# BIT_4.net
KiCad netlist of a schematic drawn in EasyEDA
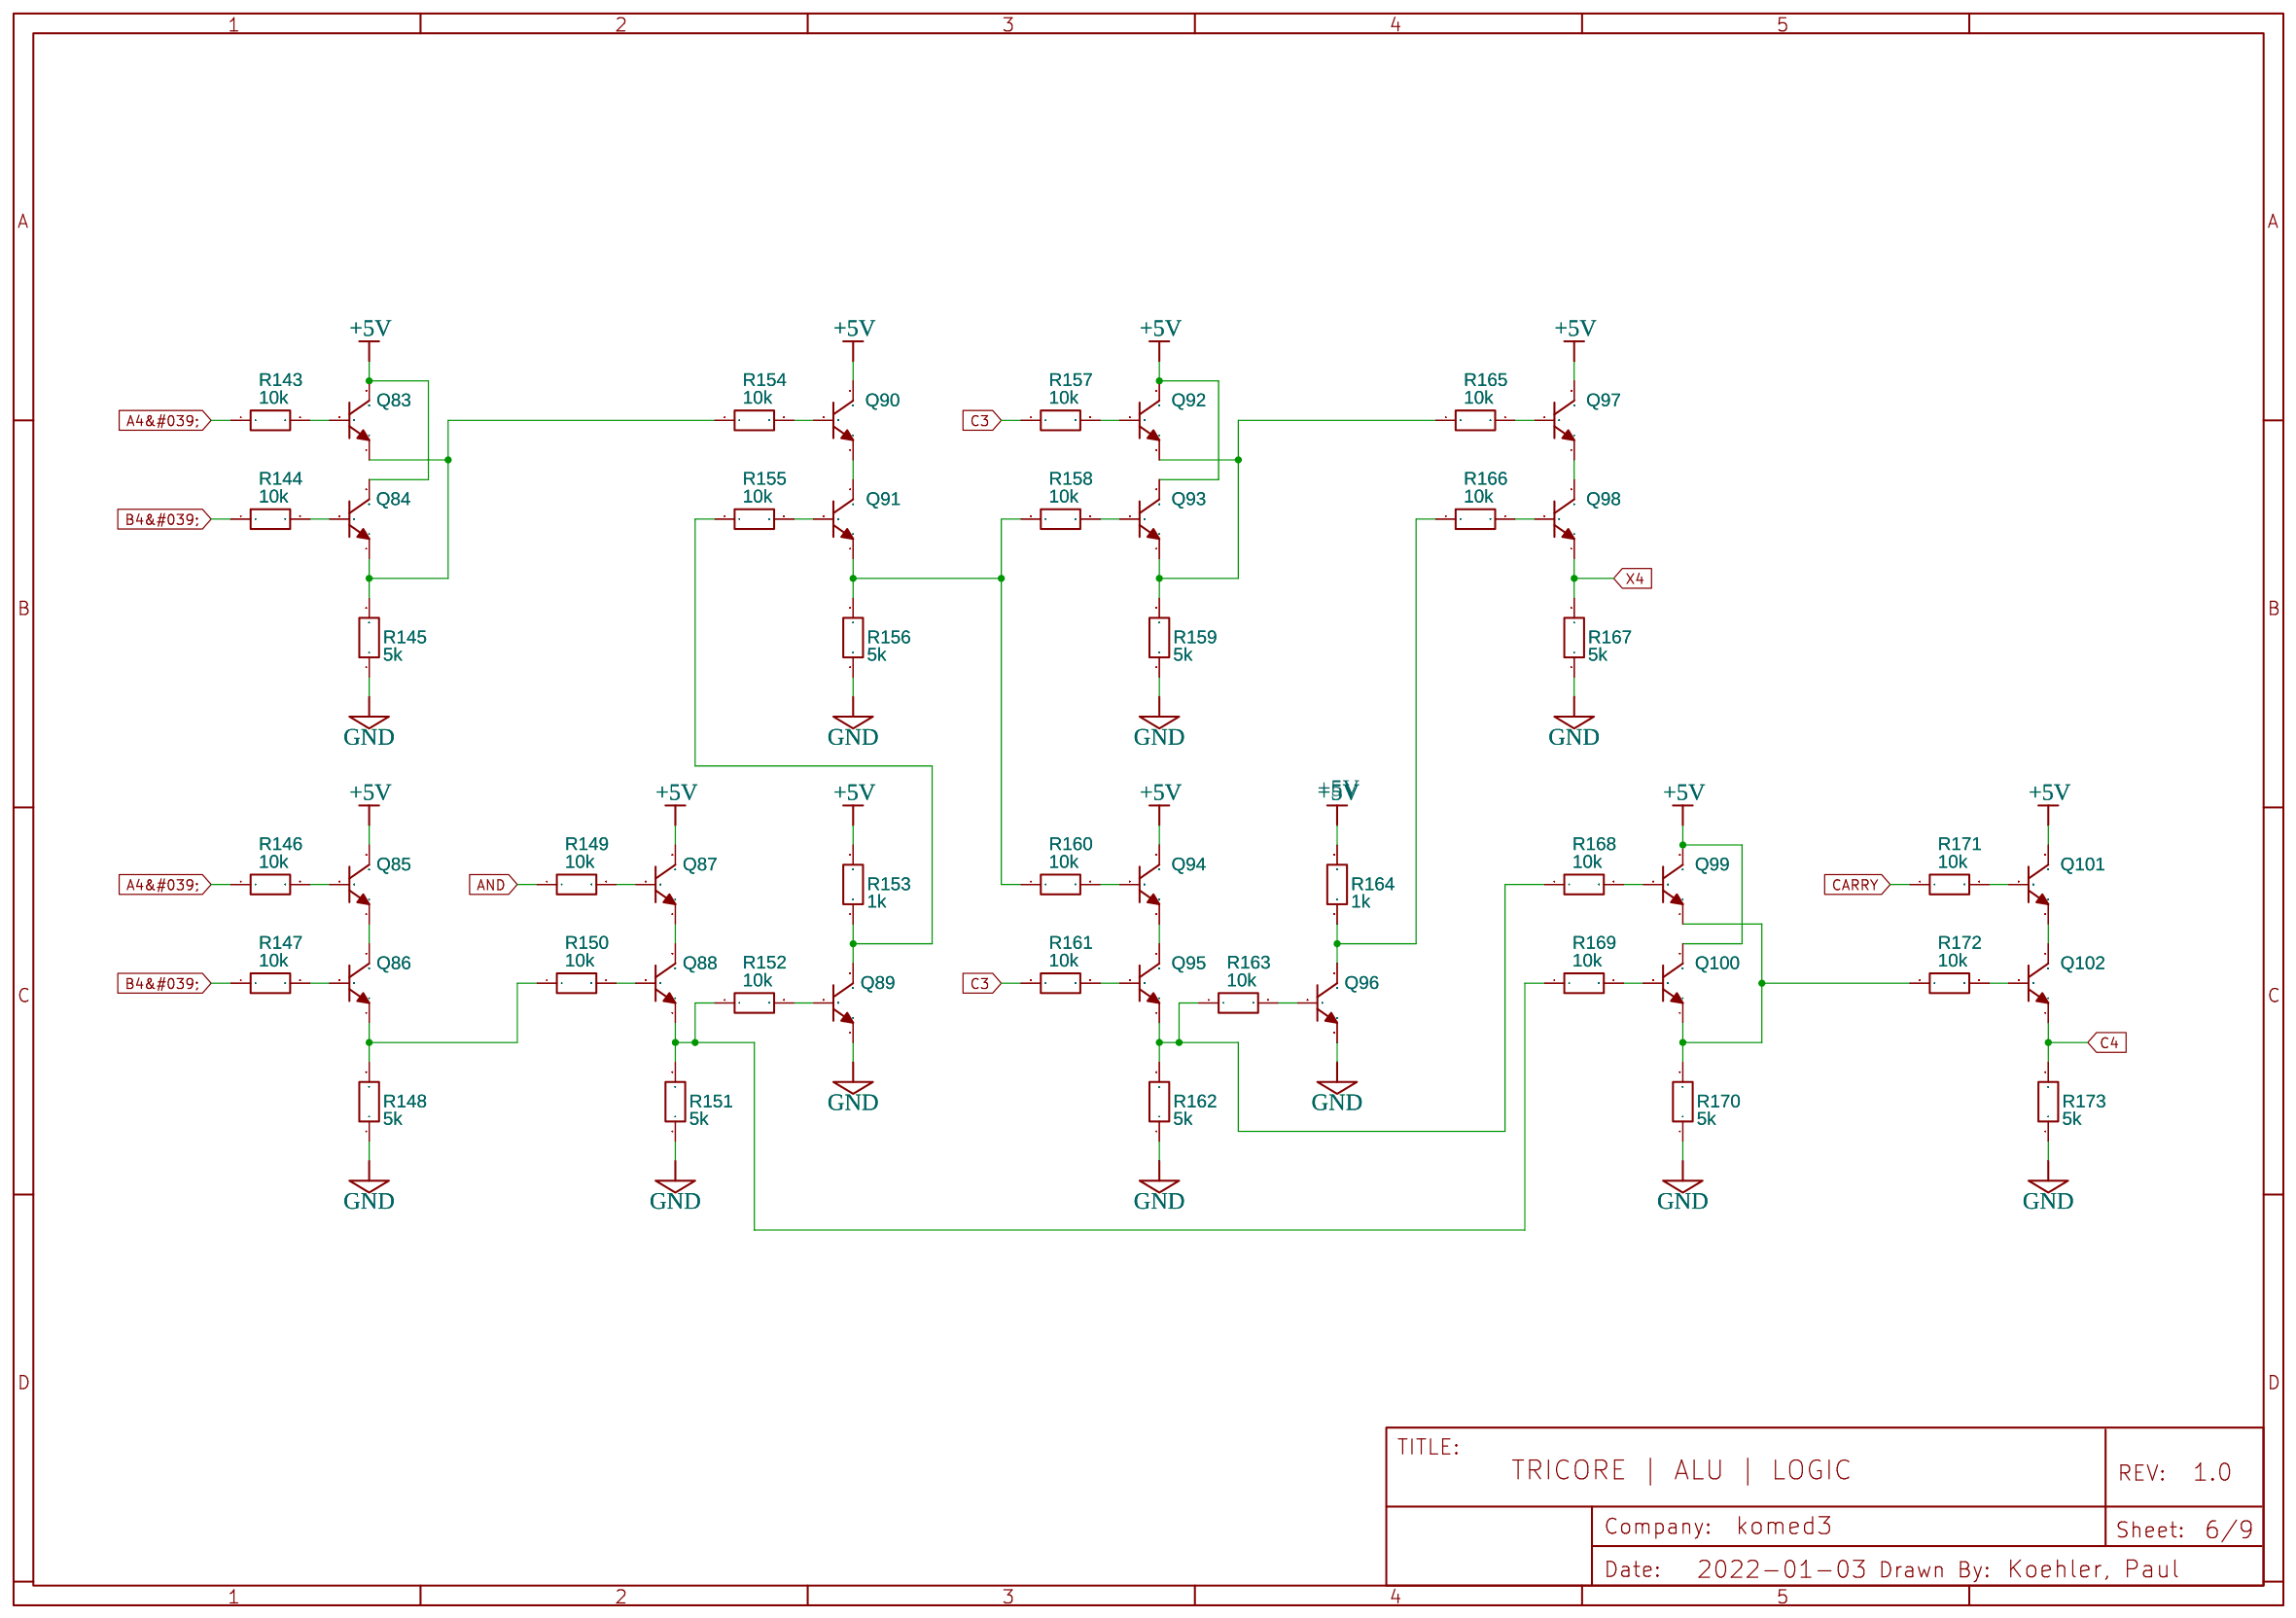
[diagram p0: schematic sheet]

(export (version "E")
  (design (tool "Eeschema 10.0.6"))
  (components
    (comp (ref "Q83")
      (value "2N3904(TO-92)")
      (fields (field (name "BOM_Manufacturer Part") "2N3904") (field (name "BOM_Supplier Part") "C118538"))
      (libsource (lib "") (part "2N3904(TO-92)"))
    )
    (comp (ref "Q84")
      (value "2N3904(TO-92)")
      (fields (field (name "BOM_Manufacturer Part") "2N3904") (field (name "BOM_Supplier Part") "C118538"))
      (libsource (lib "") (part "2N3904(TO-92)"))
    )
    (comp (ref "Q85")
      (value "2N3904(TO-92)")
      (fields (field (name "BOM_Manufacturer Part") "2N3904") (field (name "BOM_Supplier Part") "C118538"))
      (libsource (lib "") (part "2N3904(TO-92)"))
    )
    (comp (ref "Q86")
      (value "2N3904(TO-92)")
      (fields (field (name "BOM_Manufacturer Part") "2N3904") (field (name "BOM_Supplier Part") "C118538"))
      (libsource (lib "") (part "2N3904(TO-92)"))
    )
    (comp (ref "Q87")
      (value "2N3904(TO-92)")
      (fields (field (name "BOM_Manufacturer Part") "2N3904") (field (name "BOM_Supplier Part") "C118538"))
      (libsource (lib "") (part "2N3904(TO-92)"))
    )
    (comp (ref "Q88")
      (value "2N3904(TO-92)")
      (fields (field (name "BOM_Manufacturer Part") "2N3904") (field (name "BOM_Supplier Part") "C118538"))
      (libsource (lib "") (part "2N3904(TO-92)"))
    )
    (comp (ref "Q89")
      (value "2N3904(TO-92)")
      (fields (field (name "BOM_Manufacturer Part") "2N3904") (field (name "BOM_Supplier Part") "C118538"))
      (libsource (lib "") (part "2N3904(TO-92)"))
    )
    (comp (ref "Q90")
      (value "2N3904(TO-92)")
      (fields (field (name "BOM_Manufacturer Part") "2N3904") (field (name "BOM_Supplier Part") "C118538"))
      (libsource (lib "") (part "2N3904(TO-92)"))
    )
    (comp (ref "Q91")
      (value "2N3904(TO-92)")
      (fields (field (name "BOM_Manufacturer Part") "2N3904") (field (name "BOM_Supplier Part") "C118538"))
      (libsource (lib "") (part "2N3904(TO-92)"))
    )
    (comp (ref "Q92")
      (value "2N3904(TO-92)")
      (fields (field (name "BOM_Manufacturer Part") "2N3904") (field (name "BOM_Supplier Part") "C118538"))
      (libsource (lib "") (part "2N3904(TO-92)"))
    )
    (comp (ref "Q93")
      (value "2N3904(TO-92)")
      (fields (field (name "BOM_Manufacturer Part") "2N3904") (field (name "BOM_Supplier Part") "C118538"))
      (libsource (lib "") (part "2N3904(TO-92)"))
    )
    (comp (ref "Q94")
      (value "2N3904(TO-92)")
      (fields (field (name "BOM_Manufacturer Part") "2N3904") (field (name "BOM_Supplier Part") "C118538"))
      (libsource (lib "") (part "2N3904(TO-92)"))
    )
    (comp (ref "Q95")
      (value "2N3904(TO-92)")
      (fields (field (name "BOM_Manufacturer Part") "2N3904") (field (name "BOM_Supplier Part") "C118538"))
      (libsource (lib "") (part "2N3904(TO-92)"))
    )
    (comp (ref "Q96")
      (value "2N3904(TO-92)")
      (fields (field (name "BOM_Manufacturer Part") "2N3904") (field (name "BOM_Supplier Part") "C118538"))
      (libsource (lib "") (part "2N3904(TO-92)"))
    )
    (comp (ref "Q97")
      (value "2N3904(TO-92)")
      (fields (field (name "BOM_Manufacturer Part") "2N3904") (field (name "BOM_Supplier Part") "C118538"))
      (libsource (lib "") (part "2N3904(TO-92)"))
    )
    (comp (ref "Q98")
      (value "2N3904(TO-92)")
      (fields (field (name "BOM_Manufacturer Part") "2N3904") (field (name "BOM_Supplier Part") "C118538"))
      (libsource (lib "") (part "2N3904(TO-92)"))
    )
    (comp (ref "Q99")
      (value "2N3904(TO-92)")
      (fields (field (name "BOM_Manufacturer Part") "2N3904") (field (name "BOM_Supplier Part") "C118538"))
      (libsource (lib "") (part "2N3904(TO-92)"))
    )
    (comp (ref "Q100")
      (value "2N3904(TO-92)")
      (fields (field (name "BOM_Manufacturer Part") "2N3904") (field (name "BOM_Supplier Part") "C118538"))
      (libsource (lib "") (part "2N3904(TO-92)"))
    )
    (comp (ref "Q101")
      (value "2N3904(TO-92)")
      (fields (field (name "BOM_Manufacturer Part") "2N3904") (field (name "BOM_Supplier Part") "C118538"))
      (libsource (lib "") (part "2N3904(TO-92)"))
    )
    (comp (ref "Q102")
      (value "2N3904(TO-92)")
      (fields (field (name "BOM_Manufacturer Part") "2N3904") (field (name "BOM_Supplier Part") "C118538"))
      (libsource (lib "") (part "2N3904(TO-92)"))
    )
    (comp (ref "R143") (value "10k") (libsource (lib "") (part "R_AXIAL-0.3_EU_1")))
    (comp (ref "R144") (value "10k") (libsource (lib "") (part "R_AXIAL-0.3_EU_1")))
    (comp (ref "R145") (value "5k") (libsource (lib "") (part "R_AXIAL-0.3_EU")))
    (comp (ref "R146") (value "10k") (libsource (lib "") (part "R_AXIAL-0.3_EU_1")))
    (comp (ref "R147") (value "10k") (libsource (lib "") (part "R_AXIAL-0.3_EU_1")))
    (comp (ref "R148") (value "5k") (libsource (lib "") (part "R_AXIAL-0.3_EU")))
    (comp (ref "R149") (value "10k") (libsource (lib "") (part "R_AXIAL-0.3_EU_1")))
    (comp (ref "R150") (value "10k") (libsource (lib "") (part "R_AXIAL-0.3_EU_1")))
    (comp (ref "R151") (value "5k") (libsource (lib "") (part "R_AXIAL-0.3_EU")))
    (comp (ref "R152") (value "10k") (libsource (lib "") (part "R_AXIAL-0.3_EU_1")))
    (comp (ref "R153") (value "1k") (libsource (lib "") (part "R_AXIAL-0.3_EU")))
    (comp (ref "R154") (value "10k") (libsource (lib "") (part "R_AXIAL-0.3_EU_1")))
    (comp (ref "R155") (value "10k") (libsource (lib "") (part "R_AXIAL-0.3_EU_1")))
    (comp (ref "R156") (value "5k") (libsource (lib "") (part "R_AXIAL-0.3_EU")))
    (comp (ref "R157") (value "10k") (libsource (lib "") (part "R_AXIAL-0.3_EU_1")))
    (comp (ref "R158") (value "10k") (libsource (lib "") (part "R_AXIAL-0.3_EU_1")))
    (comp (ref "R159") (value "5k") (libsource (lib "") (part "R_AXIAL-0.3_EU")))
    (comp (ref "R160") (value "10k") (libsource (lib "") (part "R_AXIAL-0.3_EU_1")))
    (comp (ref "R161") (value "10k") (libsource (lib "") (part "R_AXIAL-0.3_EU_1")))
    (comp (ref "R162") (value "5k") (libsource (lib "") (part "R_AXIAL-0.3_EU")))
    (comp (ref "R163") (value "10k") (libsource (lib "") (part "R_AXIAL-0.3_EU_1")))
    (comp (ref "R164") (value "1k") (libsource (lib "") (part "R_AXIAL-0.3_EU")))
    (comp (ref "R165") (value "10k") (libsource (lib "") (part "R_AXIAL-0.3_EU_1")))
    (comp (ref "R166") (value "10k") (libsource (lib "") (part "R_AXIAL-0.3_EU_1")))
    (comp (ref "R167") (value "5k") (libsource (lib "") (part "R_AXIAL-0.3_EU")))
    (comp (ref "R168") (value "10k") (libsource (lib "") (part "R_AXIAL-0.3_EU_1")))
    (comp (ref "R169") (value "10k") (libsource (lib "") (part "R_AXIAL-0.3_EU_1")))
    (comp (ref "R170") (value "5k") (libsource (lib "") (part "R_AXIAL-0.3_EU")))
    (comp (ref "R171") (value "10k") (libsource (lib "") (part "R_AXIAL-0.3_EU_1")))
    (comp (ref "R172") (value "10k") (libsource (lib "") (part "R_AXIAL-0.3_EU_1")))
    (comp (ref "R173") (value "5k") (libsource (lib "") (part "R_AXIAL-0.3_EU")))
  )
  (nets
    (net (code "1") (name "+5V") (class "Default")
      (node (ref "Q100") (pin "3") (pinfunction "C_3") (pintype "unspecified"))
      (node (ref "Q101") (pin "3") (pinfunction "C_3") (pintype "unspecified"))
      (node (ref "Q83") (pin "3") (pinfunction "C_3") (pintype "unspecified"))
      (node (ref "Q84") (pin "3") (pinfunction "C_3") (pintype "unspecified"))
      (node (ref "Q85") (pin "3") (pinfunction "C_3") (pintype "unspecified"))
      (node (ref "Q87") (pin "3") (pinfunction "C_3") (pintype "unspecified"))
      (node (ref "Q90") (pin "3") (pinfunction "C_3") (pintype "unspecified"))
      (node (ref "Q92") (pin "3") (pinfunction "C_3") (pintype "unspecified"))
      (node (ref "Q93") (pin "3") (pinfunction "C_3") (pintype "unspecified"))
      (node (ref "Q94") (pin "3") (pinfunction "C_3") (pintype "unspecified"))
      (node (ref "Q97") (pin "3") (pinfunction "C_3") (pintype "unspecified"))
      (node (ref "Q99") (pin "3") (pinfunction "C_3") (pintype "unspecified"))
      (node (ref "R153") (pin "2") (pinfunction "2_2") (pintype "unspecified"))
      (node (ref "R164") (pin "2") (pinfunction "2_2") (pintype "unspecified"))
    )
    (net (code "2") (name "A4&#039;") (class "Default")
      (node (ref "R143") (pin "1") (pinfunction "1_1") (pintype "unspecified"))
      (node (ref "R146") (pin "1") (pinfunction "1_1") (pintype "unspecified"))
    )
    (net (code "3") (name "AND") (class "Default")
      (node (ref "R149") (pin "1") (pinfunction "1_1") (pintype "unspecified"))
    )
    (net (code "4") (name "B4&#039;") (class "Default")
      (node (ref "R144") (pin "1") (pinfunction "1_1") (pintype "unspecified"))
      (node (ref "R147") (pin "1") (pinfunction "1_1") (pintype "unspecified"))
    )
    (net (code "5") (name "C3") (class "Default")
      (node (ref "R157") (pin "1") (pinfunction "1_1") (pintype "unspecified"))
      (node (ref "R161") (pin "1") (pinfunction "1_1") (pintype "unspecified"))
    )
    (net (code "6") (name "C4") (class "Default")
      (node (ref "Q102") (pin "1") (pinfunction "E_1") (pintype "unspecified"))
      (node (ref "R173") (pin "2") (pinfunction "2_2") (pintype "unspecified"))
    )
    (net (code "7") (name "CARRY") (class "Default")
      (node (ref "R171") (pin "1") (pinfunction "1_1") (pintype "unspecified"))
    )
    (net (code "8") (name "GND") (class "Default")
      (node (ref "Q89") (pin "1") (pinfunction "E_1") (pintype "unspecified"))
      (node (ref "Q96") (pin "1") (pinfunction "E_1") (pintype "unspecified"))
      (node (ref "R145") (pin "1") (pinfunction "1_1") (pintype "unspecified"))
      (node (ref "R148") (pin "1") (pinfunction "1_1") (pintype "unspecified"))
      (node (ref "R151") (pin "1") (pinfunction "1_1") (pintype "unspecified"))
      (node (ref "R156") (pin "1") (pinfunction "1_1") (pintype "unspecified"))
      (node (ref "R159") (pin "1") (pinfunction "1_1") (pintype "unspecified"))
      (node (ref "R162") (pin "1") (pinfunction "1_1") (pintype "unspecified"))
      (node (ref "R167") (pin "1") (pinfunction "1_1") (pintype "unspecified"))
      (node (ref "R170") (pin "1") (pinfunction "1_1") (pintype "unspecified"))
      (node (ref "R173") (pin "1") (pinfunction "1_1") (pintype "unspecified"))
    )
    (net (code "9") (name "Net-(Q83-B)") (class "Default")
      (node (ref "Q83") (pin "2") (pinfunction "B_2") (pintype "unspecified"))
      (node (ref "R143") (pin "2") (pinfunction "2_2") (pintype "unspecified"))
    )
    (net (code "10") (name "Net-(Q83-E)") (class "Default")
      (node (ref "Q83") (pin "1") (pinfunction "E_1") (pintype "unspecified"))
      (node (ref "Q84") (pin "1") (pinfunction "E_1") (pintype "unspecified"))
      (node (ref "R145") (pin "2") (pinfunction "2_2") (pintype "unspecified"))
      (node (ref "R154") (pin "1") (pinfunction "1_1") (pintype "unspecified"))
    )
    (net (code "11") (name "Net-(Q84-B)") (class "Default")
      (node (ref "Q84") (pin "2") (pinfunction "B_2") (pintype "unspecified"))
      (node (ref "R144") (pin "2") (pinfunction "2_2") (pintype "unspecified"))
    )
    (net (code "12") (name "Net-(Q85-B)") (class "Default")
      (node (ref "Q85") (pin "2") (pinfunction "B_2") (pintype "unspecified"))
      (node (ref "R146") (pin "2") (pinfunction "2_2") (pintype "unspecified"))
    )
    (net (code "13") (name "Net-(Q85-E)") (class "Default")
      (node (ref "Q85") (pin "1") (pinfunction "E_1") (pintype "unspecified"))
      (node (ref "Q86") (pin "3") (pinfunction "C_3") (pintype "unspecified"))
    )
    (net (code "14") (name "Net-(Q86-B)") (class "Default")
      (node (ref "Q86") (pin "2") (pinfunction "B_2") (pintype "unspecified"))
      (node (ref "R147") (pin "2") (pinfunction "2_2") (pintype "unspecified"))
    )
    (net (code "15") (name "Net-(Q86-E)") (class "Default")
      (node (ref "Q86") (pin "1") (pinfunction "E_1") (pintype "unspecified"))
      (node (ref "R148") (pin "2") (pinfunction "2_2") (pintype "unspecified"))
      (node (ref "R150") (pin "1") (pinfunction "1_1") (pintype "unspecified"))
    )
    (net (code "16") (name "Net-(Q87-B)") (class "Default")
      (node (ref "Q87") (pin "2") (pinfunction "B_2") (pintype "unspecified"))
      (node (ref "R149") (pin "2") (pinfunction "2_2") (pintype "unspecified"))
    )
    (net (code "17") (name "Net-(Q87-E)") (class "Default")
      (node (ref "Q87") (pin "1") (pinfunction "E_1") (pintype "unspecified"))
      (node (ref "Q88") (pin "3") (pinfunction "C_3") (pintype "unspecified"))
    )
    (net (code "18") (name "Net-(Q88-B)") (class "Default")
      (node (ref "Q88") (pin "2") (pinfunction "B_2") (pintype "unspecified"))
      (node (ref "R150") (pin "2") (pinfunction "2_2") (pintype "unspecified"))
    )
    (net (code "19") (name "Net-(Q88-E)") (class "Default")
      (node (ref "Q88") (pin "1") (pinfunction "E_1") (pintype "unspecified"))
      (node (ref "R151") (pin "2") (pinfunction "2_2") (pintype "unspecified"))
      (node (ref "R152") (pin "1") (pinfunction "1_1") (pintype "unspecified"))
      (node (ref "R169") (pin "1") (pinfunction "1_1") (pintype "unspecified"))
    )
    (net (code "20") (name "Net-(Q89-B)") (class "Default")
      (node (ref "Q89") (pin "2") (pinfunction "B_2") (pintype "unspecified"))
      (node (ref "R152") (pin "2") (pinfunction "2_2") (pintype "unspecified"))
    )
    (net (code "21") (name "Net-(Q89-C)") (class "Default")
      (node (ref "Q89") (pin "3") (pinfunction "C_3") (pintype "unspecified"))
      (node (ref "R153") (pin "1") (pinfunction "1_1") (pintype "unspecified"))
      (node (ref "R155") (pin "1") (pinfunction "1_1") (pintype "unspecified"))
    )
    (net (code "22") (name "Net-(Q90-B)") (class "Default")
      (node (ref "Q90") (pin "2") (pinfunction "B_2") (pintype "unspecified"))
      (node (ref "R154") (pin "2") (pinfunction "2_2") (pintype "unspecified"))
    )
    (net (code "23") (name "Net-(Q90-E)") (class "Default")
      (node (ref "Q90") (pin "1") (pinfunction "E_1") (pintype "unspecified"))
      (node (ref "Q91") (pin "3") (pinfunction "C_3") (pintype "unspecified"))
    )
    (net (code "24") (name "Net-(Q91-B)") (class "Default")
      (node (ref "Q91") (pin "2") (pinfunction "B_2") (pintype "unspecified"))
      (node (ref "R155") (pin "2") (pinfunction "2_2") (pintype "unspecified"))
    )
    (net (code "25") (name "Net-(Q91-E)") (class "Default")
      (node (ref "Q91") (pin "1") (pinfunction "E_1") (pintype "unspecified"))
      (node (ref "R156") (pin "2") (pinfunction "2_2") (pintype "unspecified"))
      (node (ref "R158") (pin "1") (pinfunction "1_1") (pintype "unspecified"))
      (node (ref "R160") (pin "1") (pinfunction "1_1") (pintype "unspecified"))
    )
    (net (code "26") (name "Net-(Q92-B)") (class "Default")
      (node (ref "Q92") (pin "2") (pinfunction "B_2") (pintype "unspecified"))
      (node (ref "R157") (pin "2") (pinfunction "2_2") (pintype "unspecified"))
    )
    (net (code "27") (name "Net-(Q92-E)") (class "Default")
      (node (ref "Q92") (pin "1") (pinfunction "E_1") (pintype "unspecified"))
      (node (ref "Q93") (pin "1") (pinfunction "E_1") (pintype "unspecified"))
      (node (ref "R159") (pin "2") (pinfunction "2_2") (pintype "unspecified"))
      (node (ref "R165") (pin "1") (pinfunction "1_1") (pintype "unspecified"))
    )
    (net (code "28") (name "Net-(Q93-B)") (class "Default")
      (node (ref "Q93") (pin "2") (pinfunction "B_2") (pintype "unspecified"))
      (node (ref "R158") (pin "2") (pinfunction "2_2") (pintype "unspecified"))
    )
    (net (code "29") (name "Net-(Q94-B)") (class "Default")
      (node (ref "Q94") (pin "2") (pinfunction "B_2") (pintype "unspecified"))
      (node (ref "R160") (pin "2") (pinfunction "2_2") (pintype "unspecified"))
    )
    (net (code "30") (name "Net-(Q94-E)") (class "Default")
      (node (ref "Q94") (pin "1") (pinfunction "E_1") (pintype "unspecified"))
      (node (ref "Q95") (pin "3") (pinfunction "C_3") (pintype "unspecified"))
    )
    (net (code "31") (name "Net-(Q95-B)") (class "Default")
      (node (ref "Q95") (pin "2") (pinfunction "B_2") (pintype "unspecified"))
      (node (ref "R161") (pin "2") (pinfunction "2_2") (pintype "unspecified"))
    )
    (net (code "32") (name "Net-(Q95-E)") (class "Default")
      (node (ref "Q95") (pin "1") (pinfunction "E_1") (pintype "unspecified"))
      (node (ref "R162") (pin "2") (pinfunction "2_2") (pintype "unspecified"))
      (node (ref "R163") (pin "1") (pinfunction "1_1") (pintype "unspecified"))
      (node (ref "R168") (pin "1") (pinfunction "1_1") (pintype "unspecified"))
    )
    (net (code "33") (name "Net-(Q96-B)") (class "Default")
      (node (ref "Q96") (pin "2") (pinfunction "B_2") (pintype "unspecified"))
      (node (ref "R163") (pin "2") (pinfunction "2_2") (pintype "unspecified"))
    )
    (net (code "34") (name "Net-(Q96-C)") (class "Default")
      (node (ref "Q96") (pin "3") (pinfunction "C_3") (pintype "unspecified"))
      (node (ref "R164") (pin "1") (pinfunction "1_1") (pintype "unspecified"))
      (node (ref "R166") (pin "1") (pinfunction "1_1") (pintype "unspecified"))
    )
    (net (code "35") (name "Net-(Q97-B)") (class "Default")
      (node (ref "Q97") (pin "2") (pinfunction "B_2") (pintype "unspecified"))
      (node (ref "R165") (pin "2") (pinfunction "2_2") (pintype "unspecified"))
    )
    (net (code "36") (name "Net-(Q97-E)") (class "Default")
      (node (ref "Q97") (pin "1") (pinfunction "E_1") (pintype "unspecified"))
      (node (ref "Q98") (pin "3") (pinfunction "C_3") (pintype "unspecified"))
    )
    (net (code "37") (name "Net-(Q98-B)") (class "Default")
      (node (ref "Q98") (pin "2") (pinfunction "B_2") (pintype "unspecified"))
      (node (ref "R166") (pin "2") (pinfunction "2_2") (pintype "unspecified"))
    )
    (net (code "38") (name "Net-(Q99-B)") (class "Default")
      (node (ref "Q99") (pin "2") (pinfunction "B_2") (pintype "unspecified"))
      (node (ref "R168") (pin "2") (pinfunction "2_2") (pintype "unspecified"))
    )
    (net (code "39") (name "Net-(Q100-B)") (class "Default")
      (node (ref "Q100") (pin "2") (pinfunction "B_2") (pintype "unspecified"))
      (node (ref "R169") (pin "2") (pinfunction "2_2") (pintype "unspecified"))
    )
    (net (code "40") (name "Net-(Q100-E)") (class "Default")
      (node (ref "Q100") (pin "1") (pinfunction "E_1") (pintype "unspecified"))
      (node (ref "Q99") (pin "1") (pinfunction "E_1") (pintype "unspecified"))
      (node (ref "R170") (pin "2") (pinfunction "2_2") (pintype "unspecified"))
      (node (ref "R172") (pin "1") (pinfunction "1_1") (pintype "unspecified"))
    )
    (net (code "41") (name "Net-(Q101-B)") (class "Default")
      (node (ref "Q101") (pin "2") (pinfunction "B_2") (pintype "unspecified"))
      (node (ref "R171") (pin "2") (pinfunction "2_2") (pintype "unspecified"))
    )
    (net (code "42") (name "Net-(Q101-E)") (class "Default")
      (node (ref "Q101") (pin "1") (pinfunction "E_1") (pintype "unspecified"))
      (node (ref "Q102") (pin "3") (pinfunction "C_3") (pintype "unspecified"))
    )
    (net (code "43") (name "Net-(Q102-B)") (class "Default")
      (node (ref "Q102") (pin "2") (pinfunction "B_2") (pintype "unspecified"))
      (node (ref "R172") (pin "2") (pinfunction "2_2") (pintype "unspecified"))
    )
    (net (code "44") (name "X4") (class "Default")
      (node (ref "Q98") (pin "1") (pinfunction "E_1") (pintype "unspecified"))
      (node (ref "R167") (pin "2") (pinfunction "2_2") (pintype "unspecified"))
    )
  )
)
